# DS3231_RTC.net
KiCad netlist of a schematic drawn in Altium Designer
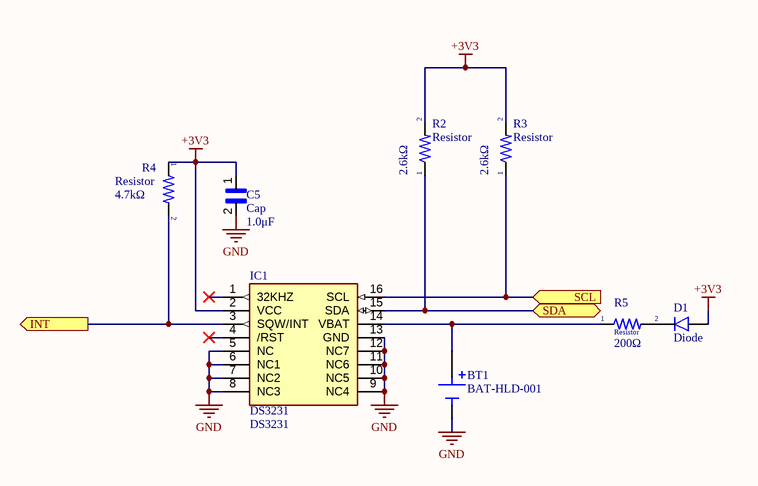
[diagram p0: DS3231_RTC.SchDoc]

(export (version "E")
  (design (tool "Eeschema 10.0.6"))
  (components
    (comp (ref "BT1")
      (value "BAT-HLD-001")
      (footprint "BAT_BAT-HLD-001")
      (description "Battery Retainer Coin, 20.0mm 1 Cell SMD (SMT) Tab")
      (libsource (lib "SLT_DL_Connectors") (part "BAT-HLD-001"))
    )
    (comp (ref "C5")
      (value "Cap")
      (footprint "Cap_0805")
      (fields (field (name "CAPACITANCE") "1.0μF"))
      (libsource (lib "SLT_DL_Discreate") (part "Cap"))
    )
    (comp (ref "D1")
      (value "Diode")
      (footprint "Diode_SMD")
      (libsource (lib "SLT_DL_Discreate") (part "Diode"))
    )
    (comp (ref "IC1")
      (value "DS3231")
      (footprint "SO16W")
      (description "Real Time Clock (RTC) IC Clock/Calendar - IÂ²C, 2-Wire Serial 8-SOIC (0.154, 3.90mm Width)")
      (fields (field (name "MF") "Maxim Integrated"))
      (libsource (lib "SLT_DL_Device") (part "DS3231"))
    )
    (comp (ref "R2")
      (value "Resistor")
      (footprint "Res_0603")
      (fields (field (name "RESISTANCE") "2.6kΩ"))
      (libsource (lib "SLT_DL_Discreate") (part "Resistor"))
    )
    (comp (ref "R3")
      (value "Resistor")
      (footprint "Res_0603")
      (fields (field (name "RESISTANCE") "2.6kΩ"))
      (libsource (lib "SLT_DL_Discreate") (part "Resistor"))
    )
    (comp (ref "R4")
      (value "Resistor")
      (footprint "Res_0603")
      (fields (field (name "RESISTANCE") "4.7kΩ"))
      (libsource (lib "SLT_DL_Discreate") (part "Resistor"))
    )
    (comp (ref "R5")
      (value "Resistor")
      (footprint "Res_0603")
      (fields (field (name "RESISTANCE") "200Ω"))
      (libsource (lib "SLT_DL_Discreate") (part "Resistor"))
    )
  )
  (nets
    (net (code "1") (name "+3V3") (class "Default")
      (node (ref "C5") (pin "1") (pinfunction "1_1") (pintype "passive"))
      (node (ref "D1") (pin "A") (pinfunction "A_A") (pintype "passive"))
      (node (ref "IC1") (pin "2") (pinfunction "VCC_2") (pintype "power_in"))
      (node (ref "R2") (pin "2") (pinfunction "2_2") (pintype "passive"))
      (node (ref "R3") (pin "2") (pinfunction "2_2") (pintype "passive"))
      (node (ref "R4") (pin "1") (pinfunction "1_1") (pintype "passive"))
    )
    (net (code "2") (name "/INT") (class "Default")
      (node (ref "IC1") (pin "3") (pinfunction "SQW/INT_3") (pintype "output"))
      (node (ref "R4") (pin "2") (pinfunction "2_2") (pintype "passive"))
    )
    (net (code "3") (name "/SCL") (class "Default")
      (node (ref "IC1") (pin "16") (pinfunction "SCL_16") (pintype "input"))
      (node (ref "R3") (pin "1") (pinfunction "1_1") (pintype "passive"))
    )
    (net (code "4") (name "/SDA") (class "Default")
      (node (ref "IC1") (pin "15") (pinfunction "SDA_15") (pintype "bidirectional"))
      (node (ref "R2") (pin "1") (pinfunction "1_1") (pintype "passive"))
    )
    (net (code "5") (name "GND") (class "Default")
      (node (ref "BT1") (pin "N-") (pinfunction "NEG_N-") (pintype "passive"))
      (node (ref "C5") (pin "2") (pinfunction "2_2") (pintype "passive"))
      (node (ref "IC1") (pin "10") (pinfunction "NC5_10") (pintype "passive"))
      (node (ref "IC1") (pin "11") (pinfunction "NC6_11") (pintype "passive"))
      (node (ref "IC1") (pin "12") (pinfunction "NC7_12") (pintype "passive"))
      (node (ref "IC1") (pin "13") (pinfunction "GND_13") (pintype "power_in"))
      (node (ref "IC1") (pin "5") (pinfunction "NC_5") (pintype "passive"))
      (node (ref "IC1") (pin "6") (pinfunction "NC1_6") (pintype "passive"))
      (node (ref "IC1") (pin "7") (pinfunction "NC2_7") (pintype "passive"))
      (node (ref "IC1") (pin "8") (pinfunction "NC3_8") (pintype "passive"))
      (node (ref "IC1") (pin "9") (pinfunction "NC4_9") (pintype "passive"))
    )
    (net (code "6") (name "Net-(BT1-POS)") (class "Default")
      (node (ref "BT1") (pin "P+") (pinfunction "POS_P+") (pintype "passive"))
      (node (ref "IC1") (pin "14") (pinfunction "VBAT_14") (pintype "power_in"))
      (node (ref "R5") (pin "1") (pinfunction "1_1") (pintype "passive"))
    )
    (net (code "7") (name "Net-(D1-PadC)") (class "Default")
      (node (ref "D1") (pin "C") (pinfunction "C_C") (pintype "passive"))
      (node (ref "R5") (pin "2") (pinfunction "2_2") (pintype "passive"))
    )
    (net (code "8") (name "unconnected-(IC1-32KHZ-Pad1)") (class "Default")
      (node (ref "IC1") (pin "1") (pinfunction "32KHZ_1") (pintype "output+no_connect"))
    )
    (net (code "9") (name "unconnected-(IC1-{slash}RST-Pad4)") (class "Default")
      (node (ref "IC1") (pin "4") (pinfunction "/RST_4") (pintype "passive+no_connect"))
    )
  )
)
